# power.net
KiCad netlist of a schematic drawn in Altium Designer
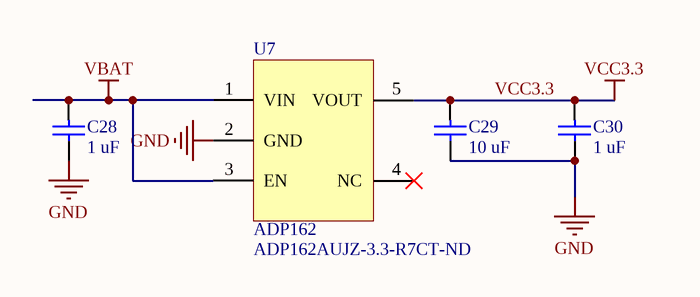
[diagram p0: power.SchDoc]

(export (version "E")
  (design (tool "Eeschema 10.0.6"))
  (components
    (comp (ref "C28")
      (value "1 uF")
      (footprint "0402")
      (description "Ceramic capacitor, 1 uF, 0402 package")
      (fields (field (name "TOLERANCE") "10%") (field (name "Comment") "Ceramic capacitor"))
      (libsource (lib "rlc") (part "C_1u_0402_ceramic"))
    )
    (comp (ref "C29")
      (value "10 uF")
      (footprint "0603")
      (description "Ceramic capacitor, 10 uF, 0603 package")
      (fields (field (name "TOLERANCE") "20%") (field (name "Comment") "Ceramic capacitor"))
      (libsource (lib "rlc") (part "C_10u_0603_ceramic"))
    )
    (comp (ref "C30")
      (value "1 uF")
      (footprint "0402")
      (description "Ceramic capacitor, 1 uF, 0402 package")
      (fields (field (name "TOLERANCE") "10%") (field (name "Comment") "Ceramic capacitor"))
      (libsource (lib "rlc") (part "C_1u_0402_ceramic"))
    )
    (comp (ref "U7")
      (value "ADP162")
      (footprint "TSOT23-5")
      (description "Ultralow Quiescent Current,  150 mA, CMOS Linear Regulators")
      (fields (field (name "SUPPLIER PART NUMBER 1") "ADP162AUJZ-3.3-R7CT-ND"))
      (libsource (lib "opo") (part "ADP162"))
    )
  )
  (nets
    (net (code "1") (name "GND") (class "Default")
      (node (ref "C28") (pin "2") (pintype "passive"))
      (node (ref "C29") (pin "2") (pintype "passive"))
      (node (ref "C30") (pin "2") (pintype "passive"))
      (node (ref "U7") (pin "2") (pinfunction "GND_2") (pintype "passive"))
    )
    (net (code "2") (name "VBAT") (class "Default")
      (node (ref "C28") (pin "1") (pintype "passive"))
      (node (ref "U7") (pin "1") (pinfunction "VIN_1") (pintype "passive"))
      (node (ref "U7") (pin "3") (pinfunction "EN_3") (pintype "passive"))
    )
    (net (code "3") (name "VCC3.3") (class "Default")
      (node (ref "C29") (pin "1") (pintype "passive"))
      (node (ref "C30") (pin "1") (pintype "passive"))
      (node (ref "U7") (pin "5") (pinfunction "VOUT_5") (pintype "passive"))
    )
    (net (code "4") (name "unconnected-(U7-NC-Pad4)") (class "Default")
      (node (ref "U7") (pin "4") (pinfunction "NC_4") (pintype "passive+no_connect"))
    )
  )
)
